# panel2.net
KiCad netlist of a schematic drawn in Altium Designer
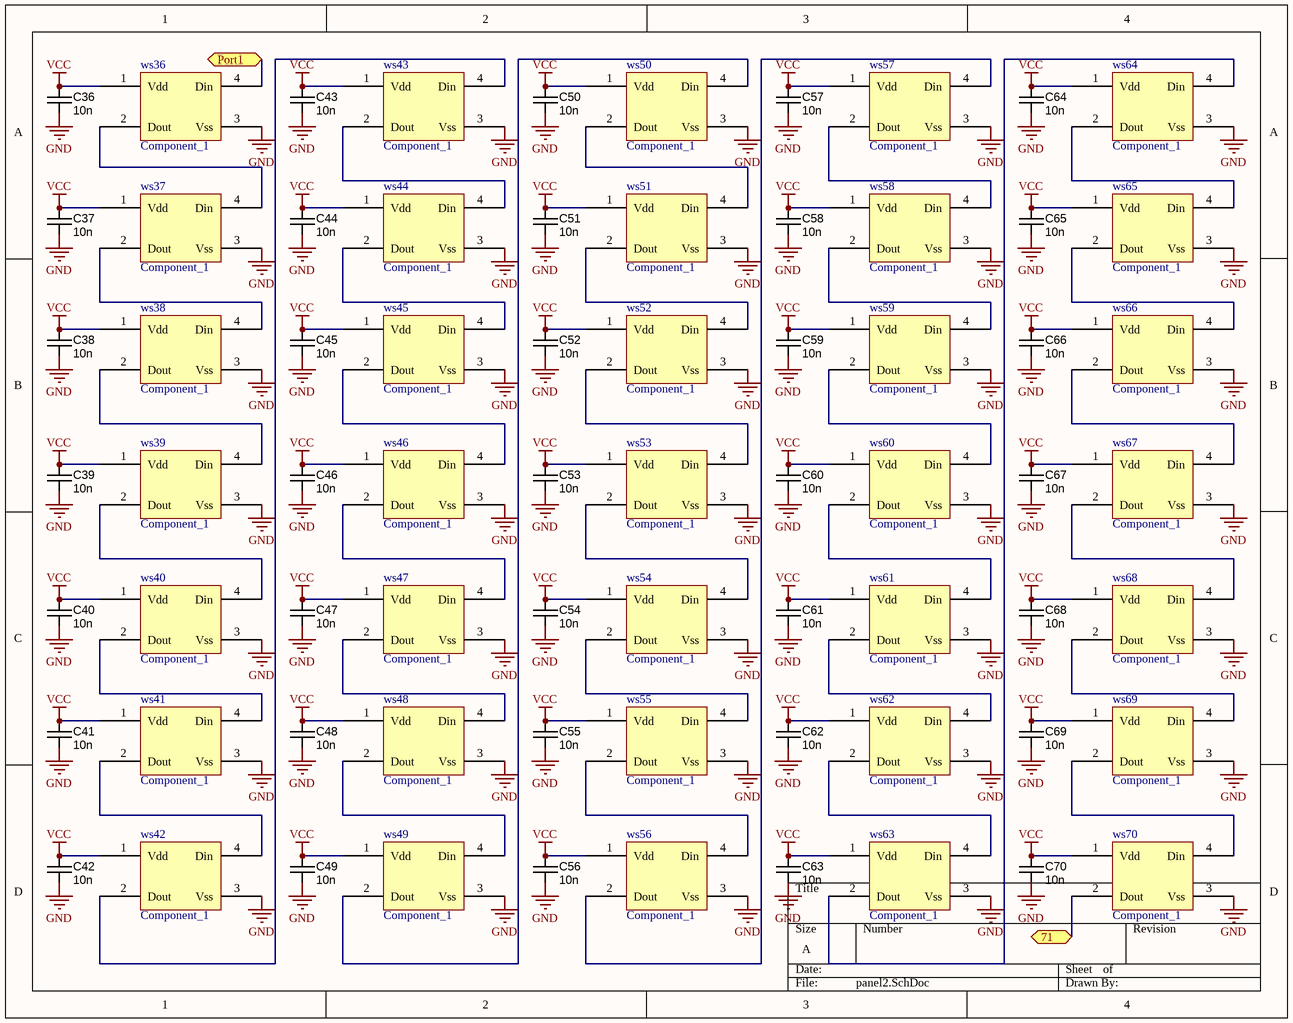
[diagram p0: panel2.SchDoc]

(export (version "E")
  (design (tool "Eeschema 10.0.6"))
  (components
    (comp (ref "C36")
      (value "10n")
      (footprint "CAPC1608X90N")
      (description "Capacitor SMD Cer 10nF 10% 100V X7R 0603")
      (fields
        (field (name "TOLERANCE") "±10%")
        (field (name "MANUFACTURER") "Murata Electronics North America")
      )
      (libsource (lib "PBL - Capacitors") (part "CAPC_10n_0603_X7R_100V_10%"))
    )
    (comp (ref "C37")
      (value "10n")
      (footprint "CAPC1608X90N")
      (description "Capacitor SMD Cer 10nF 10% 100V X7R 0603")
      (fields
        (field (name "TOLERANCE") "±10%")
        (field (name "MANUFACTURER") "Murata Electronics North America")
      )
      (libsource (lib "PBL - Capacitors") (part "CAPC_10n_0603_X7R_100V_10%"))
    )
    (comp (ref "C38")
      (value "10n")
      (footprint "CAPC1608X90N")
      (description "Capacitor SMD Cer 10nF 10% 100V X7R 0603")
      (fields
        (field (name "TOLERANCE") "±10%")
        (field (name "MANUFACTURER") "Murata Electronics North America")
      )
      (libsource (lib "PBL - Capacitors") (part "CAPC_10n_0603_X7R_100V_10%"))
    )
    (comp (ref "C39")
      (value "10n")
      (footprint "CAPC1608X90N")
      (description "Capacitor SMD Cer 10nF 10% 100V X7R 0603")
      (fields
        (field (name "TOLERANCE") "±10%")
        (field (name "MANUFACTURER") "Murata Electronics North America")
      )
      (libsource (lib "PBL - Capacitors") (part "CAPC_10n_0603_X7R_100V_10%"))
    )
    (comp (ref "C40")
      (value "10n")
      (footprint "CAPC1608X90N")
      (description "Capacitor SMD Cer 10nF 10% 100V X7R 0603")
      (fields
        (field (name "TOLERANCE") "±10%")
        (field (name "MANUFACTURER") "Murata Electronics North America")
      )
      (libsource (lib "PBL - Capacitors") (part "CAPC_10n_0603_X7R_100V_10%"))
    )
    (comp (ref "C41")
      (value "10n")
      (footprint "CAPC1608X90N")
      (description "Capacitor SMD Cer 10nF 10% 100V X7R 0603")
      (fields
        (field (name "TOLERANCE") "±10%")
        (field (name "MANUFACTURER") "Murata Electronics North America")
      )
      (libsource (lib "PBL - Capacitors") (part "CAPC_10n_0603_X7R_100V_10%"))
    )
    (comp (ref "C42")
      (value "10n")
      (footprint "CAPC1608X90N")
      (description "Capacitor SMD Cer 10nF 10% 100V X7R 0603")
      (fields
        (field (name "TOLERANCE") "±10%")
        (field (name "MANUFACTURER") "Murata Electronics North America")
      )
      (libsource (lib "PBL - Capacitors") (part "CAPC_10n_0603_X7R_100V_10%"))
    )
    (comp (ref "C43")
      (value "10n")
      (footprint "CAPC1608X90N")
      (description "Capacitor SMD Cer 10nF 10% 100V X7R 0603")
      (fields
        (field (name "TOLERANCE") "±10%")
        (field (name "MANUFACTURER") "Murata Electronics North America")
      )
      (libsource (lib "PBL - Capacitors") (part "CAPC_10n_0603_X7R_100V_10%"))
    )
    (comp (ref "C44")
      (value "10n")
      (footprint "CAPC1608X90N")
      (description "Capacitor SMD Cer 10nF 10% 100V X7R 0603")
      (fields
        (field (name "TOLERANCE") "±10%")
        (field (name "MANUFACTURER") "Murata Electronics North America")
      )
      (libsource (lib "PBL - Capacitors") (part "CAPC_10n_0603_X7R_100V_10%"))
    )
    (comp (ref "C45")
      (value "10n")
      (footprint "CAPC1608X90N")
      (description "Capacitor SMD Cer 10nF 10% 100V X7R 0603")
      (fields
        (field (name "TOLERANCE") "±10%")
        (field (name "MANUFACTURER") "Murata Electronics North America")
      )
      (libsource (lib "PBL - Capacitors") (part "CAPC_10n_0603_X7R_100V_10%"))
    )
    (comp (ref "C46")
      (value "10n")
      (footprint "CAPC1608X90N")
      (description "Capacitor SMD Cer 10nF 10% 100V X7R 0603")
      (fields
        (field (name "TOLERANCE") "±10%")
        (field (name "MANUFACTURER") "Murata Electronics North America")
      )
      (libsource (lib "PBL - Capacitors") (part "CAPC_10n_0603_X7R_100V_10%"))
    )
    (comp (ref "C47")
      (value "10n")
      (footprint "CAPC1608X90N")
      (description "Capacitor SMD Cer 10nF 10% 100V X7R 0603")
      (fields
        (field (name "TOLERANCE") "±10%")
        (field (name "MANUFACTURER") "Murata Electronics North America")
      )
      (libsource (lib "PBL - Capacitors") (part "CAPC_10n_0603_X7R_100V_10%"))
    )
    (comp (ref "C48")
      (value "10n")
      (footprint "CAPC1608X90N")
      (description "Capacitor SMD Cer 10nF 10% 100V X7R 0603")
      (fields
        (field (name "TOLERANCE") "±10%")
        (field (name "MANUFACTURER") "Murata Electronics North America")
      )
      (libsource (lib "PBL - Capacitors") (part "CAPC_10n_0603_X7R_100V_10%"))
    )
    (comp (ref "C49")
      (value "10n")
      (footprint "CAPC1608X90N")
      (description "Capacitor SMD Cer 10nF 10% 100V X7R 0603")
      (fields
        (field (name "TOLERANCE") "±10%")
        (field (name "MANUFACTURER") "Murata Electronics North America")
      )
      (libsource (lib "PBL - Capacitors") (part "CAPC_10n_0603_X7R_100V_10%"))
    )
    (comp (ref "C50")
      (value "10n")
      (footprint "CAPC1608X90N")
      (description "Capacitor SMD Cer 10nF 10% 100V X7R 0603")
      (fields
        (field (name "TOLERANCE") "±10%")
        (field (name "MANUFACTURER") "Murata Electronics North America")
      )
      (libsource (lib "PBL - Capacitors") (part "CAPC_10n_0603_X7R_100V_10%"))
    )
    (comp (ref "C51")
      (value "10n")
      (footprint "CAPC1608X90N")
      (description "Capacitor SMD Cer 10nF 10% 100V X7R 0603")
      (fields
        (field (name "TOLERANCE") "±10%")
        (field (name "MANUFACTURER") "Murata Electronics North America")
      )
      (libsource (lib "PBL - Capacitors") (part "CAPC_10n_0603_X7R_100V_10%"))
    )
    (comp (ref "C52")
      (value "10n")
      (footprint "CAPC1608X90N")
      (description "Capacitor SMD Cer 10nF 10% 100V X7R 0603")
      (fields
        (field (name "TOLERANCE") "±10%")
        (field (name "MANUFACTURER") "Murata Electronics North America")
      )
      (libsource (lib "PBL - Capacitors") (part "CAPC_10n_0603_X7R_100V_10%"))
    )
    (comp (ref "C53")
      (value "10n")
      (footprint "CAPC1608X90N")
      (description "Capacitor SMD Cer 10nF 10% 100V X7R 0603")
      (fields
        (field (name "TOLERANCE") "±10%")
        (field (name "MANUFACTURER") "Murata Electronics North America")
      )
      (libsource (lib "PBL - Capacitors") (part "CAPC_10n_0603_X7R_100V_10%"))
    )
    (comp (ref "C54")
      (value "10n")
      (footprint "CAPC1608X90N")
      (description "Capacitor SMD Cer 10nF 10% 100V X7R 0603")
      (fields
        (field (name "TOLERANCE") "±10%")
        (field (name "MANUFACTURER") "Murata Electronics North America")
      )
      (libsource (lib "PBL - Capacitors") (part "CAPC_10n_0603_X7R_100V_10%"))
    )
    (comp (ref "C55")
      (value "10n")
      (footprint "CAPC1608X90N")
      (description "Capacitor SMD Cer 10nF 10% 100V X7R 0603")
      (fields
        (field (name "TOLERANCE") "±10%")
        (field (name "MANUFACTURER") "Murata Electronics North America")
      )
      (libsource (lib "PBL - Capacitors") (part "CAPC_10n_0603_X7R_100V_10%"))
    )
    (comp (ref "C56")
      (value "10n")
      (footprint "CAPC1608X90N")
      (description "Capacitor SMD Cer 10nF 10% 100V X7R 0603")
      (fields
        (field (name "TOLERANCE") "±10%")
        (field (name "MANUFACTURER") "Murata Electronics North America")
      )
      (libsource (lib "PBL - Capacitors") (part "CAPC_10n_0603_X7R_100V_10%"))
    )
    (comp (ref "C57")
      (value "10n")
      (footprint "CAPC1608X90N")
      (description "Capacitor SMD Cer 10nF 10% 100V X7R 0603")
      (fields
        (field (name "TOLERANCE") "±10%")
        (field (name "MANUFACTURER") "Murata Electronics North America")
      )
      (libsource (lib "PBL - Capacitors") (part "CAPC_10n_0603_X7R_100V_10%"))
    )
    (comp (ref "C58")
      (value "10n")
      (footprint "CAPC1608X90N")
      (description "Capacitor SMD Cer 10nF 10% 100V X7R 0603")
      (fields
        (field (name "TOLERANCE") "±10%")
        (field (name "MANUFACTURER") "Murata Electronics North America")
      )
      (libsource (lib "PBL - Capacitors") (part "CAPC_10n_0603_X7R_100V_10%"))
    )
    (comp (ref "C59")
      (value "10n")
      (footprint "CAPC1608X90N")
      (description "Capacitor SMD Cer 10nF 10% 100V X7R 0603")
      (fields
        (field (name "TOLERANCE") "±10%")
        (field (name "MANUFACTURER") "Murata Electronics North America")
      )
      (libsource (lib "PBL - Capacitors") (part "CAPC_10n_0603_X7R_100V_10%"))
    )
    (comp (ref "C60")
      (value "10n")
      (footprint "CAPC1608X90N")
      (description "Capacitor SMD Cer 10nF 10% 100V X7R 0603")
      (fields
        (field (name "TOLERANCE") "±10%")
        (field (name "MANUFACTURER") "Murata Electronics North America")
      )
      (libsource (lib "PBL - Capacitors") (part "CAPC_10n_0603_X7R_100V_10%"))
    )
    (comp (ref "C61")
      (value "10n")
      (footprint "CAPC1608X90N")
      (description "Capacitor SMD Cer 10nF 10% 100V X7R 0603")
      (fields
        (field (name "TOLERANCE") "±10%")
        (field (name "MANUFACTURER") "Murata Electronics North America")
      )
      (libsource (lib "PBL - Capacitors") (part "CAPC_10n_0603_X7R_100V_10%"))
    )
    (comp (ref "C62")
      (value "10n")
      (footprint "CAPC1608X90N")
      (description "Capacitor SMD Cer 10nF 10% 100V X7R 0603")
      (fields
        (field (name "TOLERANCE") "±10%")
        (field (name "MANUFACTURER") "Murata Electronics North America")
      )
      (libsource (lib "PBL - Capacitors") (part "CAPC_10n_0603_X7R_100V_10%"))
    )
    (comp (ref "C63")
      (value "10n")
      (footprint "CAPC1608X90N")
      (description "Capacitor SMD Cer 10nF 10% 100V X7R 0603")
      (fields
        (field (name "TOLERANCE") "±10%")
        (field (name "MANUFACTURER") "Murata Electronics North America")
      )
      (libsource (lib "PBL - Capacitors") (part "CAPC_10n_0603_X7R_100V_10%"))
    )
    (comp (ref "C64")
      (value "10n")
      (footprint "CAPC1608X90N")
      (description "Capacitor SMD Cer 10nF 10% 100V X7R 0603")
      (fields
        (field (name "TOLERANCE") "±10%")
        (field (name "MANUFACTURER") "Murata Electronics North America")
      )
      (libsource (lib "PBL - Capacitors") (part "CAPC_10n_0603_X7R_100V_10%"))
    )
    (comp (ref "C65")
      (value "10n")
      (footprint "CAPC1608X90N")
      (description "Capacitor SMD Cer 10nF 10% 100V X7R 0603")
      (fields
        (field (name "TOLERANCE") "±10%")
        (field (name "MANUFACTURER") "Murata Electronics North America")
      )
      (libsource (lib "PBL - Capacitors") (part "CAPC_10n_0603_X7R_100V_10%"))
    )
    (comp (ref "C66")
      (value "10n")
      (footprint "CAPC1608X90N")
      (description "Capacitor SMD Cer 10nF 10% 100V X7R 0603")
      (fields
        (field (name "TOLERANCE") "±10%")
        (field (name "MANUFACTURER") "Murata Electronics North America")
      )
      (libsource (lib "PBL - Capacitors") (part "CAPC_10n_0603_X7R_100V_10%"))
    )
    (comp (ref "C67")
      (value "10n")
      (footprint "CAPC1608X90N")
      (description "Capacitor SMD Cer 10nF 10% 100V X7R 0603")
      (fields
        (field (name "TOLERANCE") "±10%")
        (field (name "MANUFACTURER") "Murata Electronics North America")
      )
      (libsource (lib "PBL - Capacitors") (part "CAPC_10n_0603_X7R_100V_10%"))
    )
    (comp (ref "C68")
      (value "10n")
      (footprint "CAPC1608X90N")
      (description "Capacitor SMD Cer 10nF 10% 100V X7R 0603")
      (fields
        (field (name "TOLERANCE") "±10%")
        (field (name "MANUFACTURER") "Murata Electronics North America")
      )
      (libsource (lib "PBL - Capacitors") (part "CAPC_10n_0603_X7R_100V_10%"))
    )
    (comp (ref "C69")
      (value "10n")
      (footprint "CAPC1608X90N")
      (description "Capacitor SMD Cer 10nF 10% 100V X7R 0603")
      (fields
        (field (name "TOLERANCE") "±10%")
        (field (name "MANUFACTURER") "Murata Electronics North America")
      )
      (libsource (lib "PBL - Capacitors") (part "CAPC_10n_0603_X7R_100V_10%"))
    )
    (comp (ref "C70")
      (value "10n")
      (footprint "CAPC1608X90N")
      (description "Capacitor SMD Cer 10nF 10% 100V X7R 0603")
      (fields
        (field (name "TOLERANCE") "±10%")
        (field (name "MANUFACTURER") "Murata Electronics North America")
      )
      (libsource (lib "PBL - Capacitors") (part "CAPC_10n_0603_X7R_100V_10%"))
    )
    (comp (ref "ws36")
      (value "Component_1")
      (footprint "SOP4")
      (libsource (lib "ws2812b") (part "Component_1"))
    )
    (comp (ref "ws37")
      (value "Component_1")
      (footprint "SOP4")
      (libsource (lib "ws2812b") (part "Component_1"))
    )
    (comp (ref "ws38")
      (value "Component_1")
      (footprint "SOP4")
      (libsource (lib "ws2812b") (part "Component_1"))
    )
    (comp (ref "ws39")
      (value "Component_1")
      (footprint "SOP4")
      (libsource (lib "ws2812b") (part "Component_1"))
    )
    (comp (ref "ws40")
      (value "Component_1")
      (footprint "SOP4")
      (libsource (lib "ws2812b") (part "Component_1"))
    )
    (comp (ref "ws41")
      (value "Component_1")
      (footprint "SOP4")
      (libsource (lib "ws2812b") (part "Component_1"))
    )
    (comp (ref "ws42")
      (value "Component_1")
      (footprint "SOP4")
      (libsource (lib "ws2812b") (part "Component_1"))
    )
    (comp (ref "ws43")
      (value "Component_1")
      (footprint "SOP4")
      (libsource (lib "ws2812b") (part "Component_1"))
    )
    (comp (ref "ws44")
      (value "Component_1")
      (footprint "SOP4")
      (libsource (lib "ws2812b") (part "Component_1"))
    )
    (comp (ref "ws45")
      (value "Component_1")
      (footprint "SOP4")
      (libsource (lib "ws2812b") (part "Component_1"))
    )
    (comp (ref "ws46")
      (value "Component_1")
      (footprint "SOP4")
      (libsource (lib "ws2812b") (part "Component_1"))
    )
    (comp (ref "ws47")
      (value "Component_1")
      (footprint "SOP4")
      (libsource (lib "ws2812b") (part "Component_1"))
    )
    (comp (ref "ws48")
      (value "Component_1")
      (footprint "SOP4")
      (libsource (lib "ws2812b") (part "Component_1"))
    )
    (comp (ref "ws49")
      (value "Component_1")
      (footprint "SOP4")
      (libsource (lib "ws2812b") (part "Component_1"))
    )
    (comp (ref "ws50")
      (value "Component_1")
      (footprint "SOP4")
      (libsource (lib "ws2812b") (part "Component_1"))
    )
    (comp (ref "ws51")
      (value "Component_1")
      (footprint "SOP4")
      (libsource (lib "ws2812b") (part "Component_1"))
    )
    (comp (ref "ws52")
      (value "Component_1")
      (footprint "SOP4")
      (libsource (lib "ws2812b") (part "Component_1"))
    )
    (comp (ref "ws53")
      (value "Component_1")
      (footprint "SOP4")
      (libsource (lib "ws2812b") (part "Component_1"))
    )
    (comp (ref "ws54")
      (value "Component_1")
      (footprint "SOP4")
      (libsource (lib "ws2812b") (part "Component_1"))
    )
    (comp (ref "ws55")
      (value "Component_1")
      (footprint "SOP4")
      (libsource (lib "ws2812b") (part "Component_1"))
    )
    (comp (ref "ws56")
      (value "Component_1")
      (footprint "SOP4")
      (libsource (lib "ws2812b") (part "Component_1"))
    )
    (comp (ref "ws57")
      (value "Component_1")
      (footprint "SOP4")
      (libsource (lib "ws2812b") (part "Component_1"))
    )
    (comp (ref "ws58")
      (value "Component_1")
      (footprint "SOP4")
      (libsource (lib "ws2812b") (part "Component_1"))
    )
    (comp (ref "ws59")
      (value "Component_1")
      (footprint "SOP4")
      (libsource (lib "ws2812b") (part "Component_1"))
    )
    (comp (ref "ws60")
      (value "Component_1")
      (footprint "SOP4")
      (libsource (lib "ws2812b") (part "Component_1"))
    )
    (comp (ref "ws61")
      (value "Component_1")
      (footprint "SOP4")
      (libsource (lib "ws2812b") (part "Component_1"))
    )
    (comp (ref "ws62")
      (value "Component_1")
      (footprint "SOP4")
      (libsource (lib "ws2812b") (part "Component_1"))
    )
    (comp (ref "ws63")
      (value "Component_1")
      (footprint "SOP4")
      (libsource (lib "ws2812b") (part "Component_1"))
    )
    (comp (ref "ws64")
      (value "Component_1")
      (footprint "SOP4")
      (libsource (lib "ws2812b") (part "Component_1"))
    )
    (comp (ref "ws65")
      (value "Component_1")
      (footprint "SOP4")
      (libsource (lib "ws2812b") (part "Component_1"))
    )
    (comp (ref "ws66")
      (value "Component_1")
      (footprint "SOP4")
      (libsource (lib "ws2812b") (part "Component_1"))
    )
    (comp (ref "ws67")
      (value "Component_1")
      (footprint "SOP4")
      (libsource (lib "ws2812b") (part "Component_1"))
    )
    (comp (ref "ws68")
      (value "Component_1")
      (footprint "SOP4")
      (libsource (lib "ws2812b") (part "Component_1"))
    )
    (comp (ref "ws69")
      (value "Component_1")
      (footprint "SOP4")
      (libsource (lib "ws2812b") (part "Component_1"))
    )
    (comp (ref "ws70")
      (value "Component_1")
      (footprint "SOP4")
      (libsource (lib "ws2812b") (part "Component_1"))
    )
  )
  (nets
    (net (code "1") (name "/71") (class "Default")
      (node (ref "ws70") (pin "2") (pinfunction "Dout_2") (pintype "passive"))
    )
    (net (code "2") (name "/Port1") (class "Default")
      (node (ref "ws36") (pin "4") (pinfunction "Din_4") (pintype "passive"))
    )
    (net (code "3") (name "GND") (class "Default")
      (node (ref "C36") (pin "2") (pintype "passive"))
      (node (ref "C37") (pin "2") (pintype "passive"))
      (node (ref "C38") (pin "2") (pintype "passive"))
      (node (ref "C39") (pin "2") (pintype "passive"))
      (node (ref "C40") (pin "2") (pintype "passive"))
      (node (ref "C41") (pin "2") (pintype "passive"))
      (node (ref "C42") (pin "2") (pintype "passive"))
      (node (ref "C43") (pin "2") (pintype "passive"))
      (node (ref "C44") (pin "2") (pintype "passive"))
      (node (ref "C45") (pin "2") (pintype "passive"))
      (node (ref "C46") (pin "2") (pintype "passive"))
      (node (ref "C47") (pin "2") (pintype "passive"))
      (node (ref "C48") (pin "2") (pintype "passive"))
      (node (ref "C49") (pin "2") (pintype "passive"))
      (node (ref "C50") (pin "2") (pintype "passive"))
      (node (ref "C51") (pin "2") (pintype "passive"))
      (node (ref "C52") (pin "2") (pintype "passive"))
      (node (ref "C53") (pin "2") (pintype "passive"))
      (node (ref "C54") (pin "2") (pintype "passive"))
      (node (ref "C55") (pin "2") (pintype "passive"))
      (node (ref "C56") (pin "2") (pintype "passive"))
      (node (ref "C57") (pin "2") (pintype "passive"))
      (node (ref "C58") (pin "2") (pintype "passive"))
      (node (ref "C59") (pin "2") (pintype "passive"))
      (node (ref "C60") (pin "2") (pintype "passive"))
      (node (ref "C61") (pin "2") (pintype "passive"))
      (node (ref "C62") (pin "2") (pintype "passive"))
      (node (ref "C63") (pin "2") (pintype "passive"))
      (node (ref "C64") (pin "2") (pintype "passive"))
      (node (ref "C65") (pin "2") (pintype "passive"))
      (node (ref "C66") (pin "2") (pintype "passive"))
      (node (ref "C67") (pin "2") (pintype "passive"))
      (node (ref "C68") (pin "2") (pintype "passive"))
      (node (ref "C69") (pin "2") (pintype "passive"))
      (node (ref "C70") (pin "2") (pintype "passive"))
      (node (ref "ws36") (pin "3") (pinfunction "Vss_3") (pintype "passive"))
      (node (ref "ws37") (pin "3") (pinfunction "Vss_3") (pintype "passive"))
      (node (ref "ws38") (pin "3") (pinfunction "Vss_3") (pintype "passive"))
      (node (ref "ws39") (pin "3") (pinfunction "Vss_3") (pintype "passive"))
      (node (ref "ws40") (pin "3") (pinfunction "Vss_3") (pintype "passive"))
      (node (ref "ws41") (pin "3") (pinfunction "Vss_3") (pintype "passive"))
      (node (ref "ws42") (pin "3") (pinfunction "Vss_3") (pintype "passive"))
      (node (ref "ws43") (pin "3") (pinfunction "Vss_3") (pintype "passive"))
      (node (ref "ws44") (pin "3") (pinfunction "Vss_3") (pintype "passive"))
      (node (ref "ws45") (pin "3") (pinfunction "Vss_3") (pintype "passive"))
      (node (ref "ws46") (pin "3") (pinfunction "Vss_3") (pintype "passive"))
      (node (ref "ws47") (pin "3") (pinfunction "Vss_3") (pintype "passive"))
      (node (ref "ws48") (pin "3") (pinfunction "Vss_3") (pintype "passive"))
      (node (ref "ws49") (pin "3") (pinfunction "Vss_3") (pintype "passive"))
      (node (ref "ws50") (pin "3") (pinfunction "Vss_3") (pintype "passive"))
      (node (ref "ws51") (pin "3") (pinfunction "Vss_3") (pintype "passive"))
      (node (ref "ws52") (pin "3") (pinfunction "Vss_3") (pintype "passive"))
      (node (ref "ws53") (pin "3") (pinfunction "Vss_3") (pintype "passive"))
      (node (ref "ws54") (pin "3") (pinfunction "Vss_3") (pintype "passive"))
      (node (ref "ws55") (pin "3") (pinfunction "Vss_3") (pintype "passive"))
      (node (ref "ws56") (pin "3") (pinfunction "Vss_3") (pintype "passive"))
      (node (ref "ws57") (pin "3") (pinfunction "Vss_3") (pintype "passive"))
      (node (ref "ws58") (pin "3") (pinfunction "Vss_3") (pintype "passive"))
      (node (ref "ws59") (pin "3") (pinfunction "Vss_3") (pintype "passive"))
      (node (ref "ws60") (pin "3") (pinfunction "Vss_3") (pintype "passive"))
      (node (ref "ws61") (pin "3") (pinfunction "Vss_3") (pintype "passive"))
      (node (ref "ws62") (pin "3") (pinfunction "Vss_3") (pintype "passive"))
      (node (ref "ws63") (pin "3") (pinfunction "Vss_3") (pintype "passive"))
      (node (ref "ws64") (pin "3") (pinfunction "Vss_3") (pintype "passive"))
      (node (ref "ws65") (pin "3") (pinfunction "Vss_3") (pintype "passive"))
      (node (ref "ws66") (pin "3") (pinfunction "Vss_3") (pintype "passive"))
      (node (ref "ws67") (pin "3") (pinfunction "Vss_3") (pintype "passive"))
      (node (ref "ws68") (pin "3") (pinfunction "Vss_3") (pintype "passive"))
      (node (ref "ws69") (pin "3") (pinfunction "Vss_3") (pintype "passive"))
      (node (ref "ws70") (pin "3") (pinfunction "Vss_3") (pintype "passive"))
    )
    (net (code "4") (name "Net-(ws36-Dout)") (class "Default")
      (node (ref "ws36") (pin "2") (pinfunction "Dout_2") (pintype "passive"))
      (node (ref "ws37") (pin "4") (pinfunction "Din_4") (pintype "passive"))
    )
    (net (code "5") (name "Net-(ws37-Dout)") (class "Default")
      (node (ref "ws37") (pin "2") (pinfunction "Dout_2") (pintype "passive"))
      (node (ref "ws38") (pin "4") (pinfunction "Din_4") (pintype "passive"))
    )
    (net (code "6") (name "Net-(ws38-Dout)") (class "Default")
      (node (ref "ws38") (pin "2") (pinfunction "Dout_2") (pintype "passive"))
      (node (ref "ws39") (pin "4") (pinfunction "Din_4") (pintype "passive"))
    )
    (net (code "7") (name "Net-(ws39-Dout)") (class "Default")
      (node (ref "ws39") (pin "2") (pinfunction "Dout_2") (pintype "passive"))
      (node (ref "ws40") (pin "4") (pinfunction "Din_4") (pintype "passive"))
    )
    (net (code "8") (name "Net-(ws40-Dout)") (class "Default")
      (node (ref "ws40") (pin "2") (pinfunction "Dout_2") (pintype "passive"))
      (node (ref "ws41") (pin "4") (pinfunction "Din_4") (pintype "passive"))
    )
    (net (code "9") (name "Net-(ws41-Dout)") (class "Default")
      (node (ref "ws41") (pin "2") (pinfunction "Dout_2") (pintype "passive"))
      (node (ref "ws42") (pin "4") (pinfunction "Din_4") (pintype "passive"))
    )
    (net (code "10") (name "Net-(ws42-Dout)") (class "Default")
      (node (ref "ws42") (pin "2") (pinfunction "Dout_2") (pintype "passive"))
      (node (ref "ws43") (pin "4") (pinfunction "Din_4") (pintype "passive"))
    )
    (net (code "11") (name "Net-(ws43-Dout)") (class "Default")
      (node (ref "ws43") (pin "2") (pinfunction "Dout_2") (pintype "passive"))
      (node (ref "ws44") (pin "4") (pinfunction "Din_4") (pintype "passive"))
    )
    (net (code "12") (name "Net-(ws44-Dout)") (class "Default")
      (node (ref "ws44") (pin "2") (pinfunction "Dout_2") (pintype "passive"))
      (node (ref "ws45") (pin "4") (pinfunction "Din_4") (pintype "passive"))
    )
    (net (code "13") (name "Net-(ws45-Dout)") (class "Default")
      (node (ref "ws45") (pin "2") (pinfunction "Dout_2") (pintype "passive"))
      (node (ref "ws46") (pin "4") (pinfunction "Din_4") (pintype "passive"))
    )
    (net (code "14") (name "Net-(ws46-Dout)") (class "Default")
      (node (ref "ws46") (pin "2") (pinfunction "Dout_2") (pintype "passive"))
      (node (ref "ws47") (pin "4") (pinfunction "Din_4") (pintype "passive"))
    )
    (net (code "15") (name "Net-(ws47-Dout)") (class "Default")
      (node (ref "ws47") (pin "2") (pinfunction "Dout_2") (pintype "passive"))
      (node (ref "ws48") (pin "4") (pinfunction "Din_4") (pintype "passive"))
    )
    (net (code "16") (name "Net-(ws48-Dout)") (class "Default")
      (node (ref "ws48") (pin "2") (pinfunction "Dout_2") (pintype "passive"))
      (node (ref "ws49") (pin "4") (pinfunction "Din_4") (pintype "passive"))
    )
    (net (code "17") (name "Net-(ws49-Dout)") (class "Default")
      (node (ref "ws49") (pin "2") (pinfunction "Dout_2") (pintype "passive"))
      (node (ref "ws50") (pin "4") (pinfunction "Din_4") (pintype "passive"))
    )
    (net (code "18") (name "Net-(ws50-Dout)") (class "Default")
      (node (ref "ws50") (pin "2") (pinfunction "Dout_2") (pintype "passive"))
      (node (ref "ws51") (pin "4") (pinfunction "Din_4") (pintype "passive"))
    )
    (net (code "19") (name "Net-(ws51-Dout)") (class "Default")
      (node (ref "ws51") (pin "2") (pinfunction "Dout_2") (pintype "passive"))
      (node (ref "ws52") (pin "4") (pinfunction "Din_4") (pintype "passive"))
    )
    (net (code "20") (name "Net-(ws52-Dout)") (class "Default")
      (node (ref "ws52") (pin "2") (pinfunction "Dout_2") (pintype "passive"))
      (node (ref "ws53") (pin "4") (pinfunction "Din_4") (pintype "passive"))
    )
    (net (code "21") (name "Net-(ws53-Dout)") (class "Default")
      (node (ref "ws53") (pin "2") (pinfunction "Dout_2") (pintype "passive"))
      (node (ref "ws54") (pin "4") (pinfunction "Din_4") (pintype "passive"))
    )
    (net (code "22") (name "Net-(ws54-Dout)") (class "Default")
      (node (ref "ws54") (pin "2") (pinfunction "Dout_2") (pintype "passive"))
      (node (ref "ws55") (pin "4") (pinfunction "Din_4") (pintype "passive"))
    )
    (net (code "23") (name "Net-(ws55-Dout)") (class "Default")
      (node (ref "ws55") (pin "2") (pinfunction "Dout_2") (pintype "passive"))
      (node (ref "ws56") (pin "4") (pinfunction "Din_4") (pintype "passive"))
    )
    (net (code "24") (name "Net-(ws56-Dout)") (class "Default")
      (node (ref "ws56") (pin "2") (pinfunction "Dout_2") (pintype "passive"))
      (node (ref "ws57") (pin "4") (pinfunction "Din_4") (pintype "passive"))
    )
    (net (code "25") (name "Net-(ws57-Dout)") (class "Default")
      (node (ref "ws57") (pin "2") (pinfunction "Dout_2") (pintype "passive"))
      (node (ref "ws58") (pin "4") (pinfunction "Din_4") (pintype "passive"))
    )
    (net (code "26") (name "Net-(ws58-Dout)") (class "Default")
      (node (ref "ws58") (pin "2") (pinfunction "Dout_2") (pintype "passive"))
      (node (ref "ws59") (pin "4") (pinfunction "Din_4") (pintype "passive"))
    )
    (net (code "27") (name "Net-(ws59-Dout)") (class "Default")
      (node (ref "ws59") (pin "2") (pinfunction "Dout_2") (pintype "passive"))
      (node (ref "ws60") (pin "4") (pinfunction "Din_4") (pintype "passive"))
    )
    (net (code "28") (name "Net-(ws60-Dout)") (class "Default")
      (node (ref "ws60") (pin "2") (pinfunction "Dout_2") (pintype "passive"))
      (node (ref "ws61") (pin "4") (pinfunction "Din_4") (pintype "passive"))
    )
    (net (code "29") (name "Net-(ws61-Dout)") (class "Default")
      (node (ref "ws61") (pin "2") (pinfunction "Dout_2") (pintype "passive"))
      (node (ref "ws62") (pin "4") (pinfunction "Din_4") (pintype "passive"))
    )
    (net (code "30") (name "Net-(ws62-Dout)") (class "Default")
      (node (ref "ws62") (pin "2") (pinfunction "Dout_2") (pintype "passive"))
      (node (ref "ws63") (pin "4") (pinfunction "Din_4") (pintype "passive"))
    )
    (net (code "31") (name "Net-(ws63-Dout)") (class "Default")
      (node (ref "ws63") (pin "2") (pinfunction "Dout_2") (pintype "passive"))
      (node (ref "ws64") (pin "4") (pinfunction "Din_4") (pintype "passive"))
    )
    (net (code "32") (name "Net-(ws64-Dout)") (class "Default")
      (node (ref "ws64") (pin "2") (pinfunction "Dout_2") (pintype "passive"))
      (node (ref "ws65") (pin "4") (pinfunction "Din_4") (pintype "passive"))
    )
    (net (code "33") (name "Net-(ws65-Dout)") (class "Default")
      (node (ref "ws65") (pin "2") (pinfunction "Dout_2") (pintype "passive"))
      (node (ref "ws66") (pin "4") (pinfunction "Din_4") (pintype "passive"))
    )
    (net (code "34") (name "Net-(ws66-Dout)") (class "Default")
      (node (ref "ws66") (pin "2") (pinfunction "Dout_2") (pintype "passive"))
      (node (ref "ws67") (pin "4") (pinfunction "Din_4") (pintype "passive"))
    )
    (net (code "35") (name "Net-(ws67-Dout)") (class "Default")
      (node (ref "ws67") (pin "2") (pinfunction "Dout_2") (pintype "passive"))
      (node (ref "ws68") (pin "4") (pinfunction "Din_4") (pintype "passive"))
    )
    (net (code "36") (name "Net-(ws68-Dout)") (class "Default")
      (node (ref "ws68") (pin "2") (pinfunction "Dout_2") (pintype "passive"))
      (node (ref "ws69") (pin "4") (pinfunction "Din_4") (pintype "passive"))
    )
    (net (code "37") (name "Net-(ws69-Dout)") (class "Default")
      (node (ref "ws69") (pin "2") (pinfunction "Dout_2") (pintype "passive"))
      (node (ref "ws70") (pin "4") (pinfunction "Din_4") (pintype "passive"))
    )
    (net (code "38") (name "VCC") (class "Default")
      (node (ref "C36") (pin "1") (pintype "passive"))
      (node (ref "C37") (pin "1") (pintype "passive"))
      (node (ref "C38") (pin "1") (pintype "passive"))
      (node (ref "C39") (pin "1") (pintype "passive"))
      (node (ref "C40") (pin "1") (pintype "passive"))
      (node (ref "C41") (pin "1") (pintype "passive"))
      (node (ref "C42") (pin "1") (pintype "passive"))
      (node (ref "C43") (pin "1") (pintype "passive"))
      (node (ref "C44") (pin "1") (pintype "passive"))
      (node (ref "C45") (pin "1") (pintype "passive"))
      (node (ref "C46") (pin "1") (pintype "passive"))
      (node (ref "C47") (pin "1") (pintype "passive"))
      (node (ref "C48") (pin "1") (pintype "passive"))
      (node (ref "C49") (pin "1") (pintype "passive"))
      (node (ref "C50") (pin "1") (pintype "passive"))
      (node (ref "C51") (pin "1") (pintype "passive"))
      (node (ref "C52") (pin "1") (pintype "passive"))
      (node (ref "C53") (pin "1") (pintype "passive"))
      (node (ref "C54") (pin "1") (pintype "passive"))
      (node (ref "C55") (pin "1") (pintype "passive"))
      (node (ref "C56") (pin "1") (pintype "passive"))
      (node (ref "C57") (pin "1") (pintype "passive"))
      (node (ref "C58") (pin "1") (pintype "passive"))
      (node (ref "C59") (pin "1") (pintype "passive"))
      (node (ref "C60") (pin "1") (pintype "passive"))
      (node (ref "C61") (pin "1") (pintype "passive"))
      (node (ref "C62") (pin "1") (pintype "passive"))
      (node (ref "C63") (pin "1") (pintype "passive"))
      (node (ref "C64") (pin "1") (pintype "passive"))
      (node (ref "C65") (pin "1") (pintype "passive"))
      (node (ref "C66") (pin "1") (pintype "passive"))
      (node (ref "C67") (pin "1") (pintype "passive"))
      (node (ref "C68") (pin "1") (pintype "passive"))
      (node (ref "C69") (pin "1") (pintype "passive"))
      (node (ref "C70") (pin "1") (pintype "passive"))
      (node (ref "ws36") (pin "1") (pinfunction "Vdd_1") (pintype "passive"))
      (node (ref "ws37") (pin "1") (pinfunction "Vdd_1") (pintype "passive"))
      (node (ref "ws38") (pin "1") (pinfunction "Vdd_1") (pintype "passive"))
      (node (ref "ws39") (pin "1") (pinfunction "Vdd_1") (pintype "passive"))
      (node (ref "ws40") (pin "1") (pinfunction "Vdd_1") (pintype "passive"))
      (node (ref "ws41") (pin "1") (pinfunction "Vdd_1") (pintype "passive"))
      (node (ref "ws42") (pin "1") (pinfunction "Vdd_1") (pintype "passive"))
      (node (ref "ws43") (pin "1") (pinfunction "Vdd_1") (pintype "passive"))
      (node (ref "ws44") (pin "1") (pinfunction "Vdd_1") (pintype "passive"))
      (node (ref "ws45") (pin "1") (pinfunction "Vdd_1") (pintype "passive"))
      (node (ref "ws46") (pin "1") (pinfunction "Vdd_1") (pintype "passive"))
      (node (ref "ws47") (pin "1") (pinfunction "Vdd_1") (pintype "passive"))
      (node (ref "ws48") (pin "1") (pinfunction "Vdd_1") (pintype "passive"))
      (node (ref "ws49") (pin "1") (pinfunction "Vdd_1") (pintype "passive"))
      (node (ref "ws50") (pin "1") (pinfunction "Vdd_1") (pintype "passive"))
      (node (ref "ws51") (pin "1") (pinfunction "Vdd_1") (pintype "passive"))
      (node (ref "ws52") (pin "1") (pinfunction "Vdd_1") (pintype "passive"))
      (node (ref "ws53") (pin "1") (pinfunction "Vdd_1") (pintype "passive"))
      (node (ref "ws54") (pin "1") (pinfunction "Vdd_1") (pintype "passive"))
      (node (ref "ws55") (pin "1") (pinfunction "Vdd_1") (pintype "passive"))
      (node (ref "ws56") (pin "1") (pinfunction "Vdd_1") (pintype "passive"))
      (node (ref "ws57") (pin "1") (pinfunction "Vdd_1") (pintype "passive"))
      (node (ref "ws58") (pin "1") (pinfunction "Vdd_1") (pintype "passive"))
      (node (ref "ws59") (pin "1") (pinfunction "Vdd_1") (pintype "passive"))
      (node (ref "ws60") (pin "1") (pinfunction "Vdd_1") (pintype "passive"))
      (node (ref "ws61") (pin "1") (pinfunction "Vdd_1") (pintype "passive"))
      (node (ref "ws62") (pin "1") (pinfunction "Vdd_1") (pintype "passive"))
      (node (ref "ws63") (pin "1") (pinfunction "Vdd_1") (pintype "passive"))
      (node (ref "ws64") (pin "1") (pinfunction "Vdd_1") (pintype "passive"))
      (node (ref "ws65") (pin "1") (pinfunction "Vdd_1") (pintype "passive"))
      (node (ref "ws66") (pin "1") (pinfunction "Vdd_1") (pintype "passive"))
      (node (ref "ws67") (pin "1") (pinfunction "Vdd_1") (pintype "passive"))
      (node (ref "ws68") (pin "1") (pinfunction "Vdd_1") (pintype "passive"))
      (node (ref "ws69") (pin "1") (pinfunction "Vdd_1") (pintype "passive"))
      (node (ref "ws70") (pin "1") (pinfunction "Vdd_1") (pintype "passive"))
    )
  )
)
